# bq32000.net
KiCad netlist of a schematic drawn in EAGLE
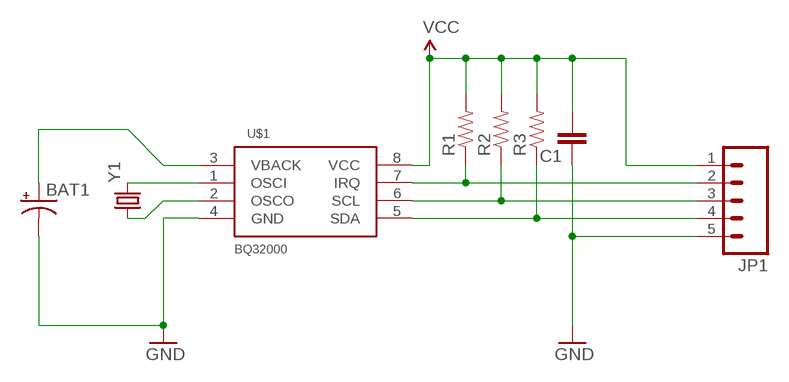
[diagram p0: schematic, sheet 1]

(export (version "E")
  (design (tool "Eeschema 10.0.6"))
  (components
    (comp (ref "BAT1")
      (value "CAP_POLPTH3")
      (footprint "eagle-import:CPOL-RADIAL-1000UF-63V")
      (libsource (lib "eagle-import") (part "CAP_POLPTH3"))
    )
    (comp (ref "C1")
      (value "CAP0805")
      (footprint "eagle-import:0805")
      (libsource (lib "eagle-import") (part "CAP0805"))
    )
    (comp (ref "JP1")
      (value "M05LOCK")
      (footprint "eagle-import:1X05_LOCK")
      (libsource (lib "eagle-import") (part "M05LOCK"))
    )
    (comp (ref "R1")
      (value "RESISTOR0805-RES")
      (footprint "eagle-import:0805")
      (libsource (lib "eagle-import") (part "RESISTOR0805-RES"))
    )
    (comp (ref "R2")
      (value "RESISTOR0805-RES")
      (footprint "eagle-import:0805")
      (libsource (lib "eagle-import") (part "RESISTOR0805-RES"))
    )
    (comp (ref "R3")
      (value "RESISTOR0805-RES")
      (footprint "eagle-import:0805")
      (libsource (lib "eagle-import") (part "RESISTOR0805-RES"))
    )
    (comp (ref "U$1")
      (value "BQ32000")
      (footprint "eagle-import:SO08")
      (libsource (lib "eagle-import") (part "BQ32000"))
    )
    (comp (ref "Y1")
      (value "CRYSTAL32-SMD")
      (footprint "eagle-import:CRYSTAL-32KHZ-SMD")
      (libsource (lib "eagle-import") (part "CRYSTAL32-SMD"))
    )
  )
  (nets
    (net (code "1") (name "GND") (class "Default")
      (node (ref "BAT1") (pin "2") (pinfunction "-_2") (pintype "passive"))
      (node (ref "C1") (pin "1") (pinfunction "1_1") (pintype "passive"))
      (node (ref "JP1") (pin "5") (pinfunction "5_5") (pintype "passive"))
      (node (ref "U$1") (pin "4") (pinfunction "GND_4") (pintype "bidirectional"))
    )
    (net (code "2") (name "Net-(BAT1-+)") (class "Default")
      (node (ref "BAT1") (pin "1") (pinfunction "+_1") (pintype "passive"))
      (node (ref "U$1") (pin "3") (pinfunction "VBACK_3") (pintype "bidirectional"))
    )
    (net (code "3") (name "Net-(U$1-IRQ)") (class "Default")
      (node (ref "JP1") (pin "2") (pinfunction "2_2") (pintype "passive"))
      (node (ref "R1") (pin "1") (pinfunction "1_1") (pintype "passive"))
      (node (ref "U$1") (pin "7") (pinfunction "IRQ_7") (pintype "output"))
    )
    (net (code "4") (name "Net-(U$1-OSCI)") (class "Default")
      (node (ref "U$1") (pin "1") (pinfunction "OSCI_1") (pintype "bidirectional"))
      (node (ref "Y1") (pin "X2") (pinfunction "2_X2") (pintype "passive"))
    )
    (net (code "5") (name "Net-(U$1-OSCO)") (class "Default")
      (node (ref "U$1") (pin "2") (pinfunction "OSCO_2") (pintype "bidirectional"))
      (node (ref "Y1") (pin "X1") (pinfunction "1_X1") (pintype "passive"))
    )
    (net (code "6") (name "Net-(U$1-SCL)") (class "Default")
      (node (ref "JP1") (pin "3") (pinfunction "3_3") (pintype "passive"))
      (node (ref "R2") (pin "1") (pinfunction "1_1") (pintype "passive"))
      (node (ref "U$1") (pin "6") (pinfunction "SCL_6") (pintype "input"))
    )
    (net (code "7") (name "Net-(U$1-SDA)") (class "Default")
      (node (ref "JP1") (pin "4") (pinfunction "4_4") (pintype "passive"))
      (node (ref "R3") (pin "1") (pinfunction "1_1") (pintype "passive"))
      (node (ref "U$1") (pin "5") (pinfunction "SDA_5") (pintype "bidirectional"))
    )
    (net (code "8") (name "VCC") (class "Default")
      (node (ref "C1") (pin "2") (pinfunction "2_2") (pintype "passive"))
      (node (ref "JP1") (pin "1") (pinfunction "1_1") (pintype "passive"))
      (node (ref "R1") (pin "2") (pinfunction "2_2") (pintype "passive"))
      (node (ref "R2") (pin "2") (pinfunction "2_2") (pintype "passive"))
      (node (ref "R3") (pin "2") (pinfunction "2_2") (pintype "passive"))
      (node (ref "U$1") (pin "8") (pinfunction "VCC_8") (pintype "power_in"))
    )
  )
)
